# schachzwerg.net
KiCad netlist of a schematic drawn in EAGLE
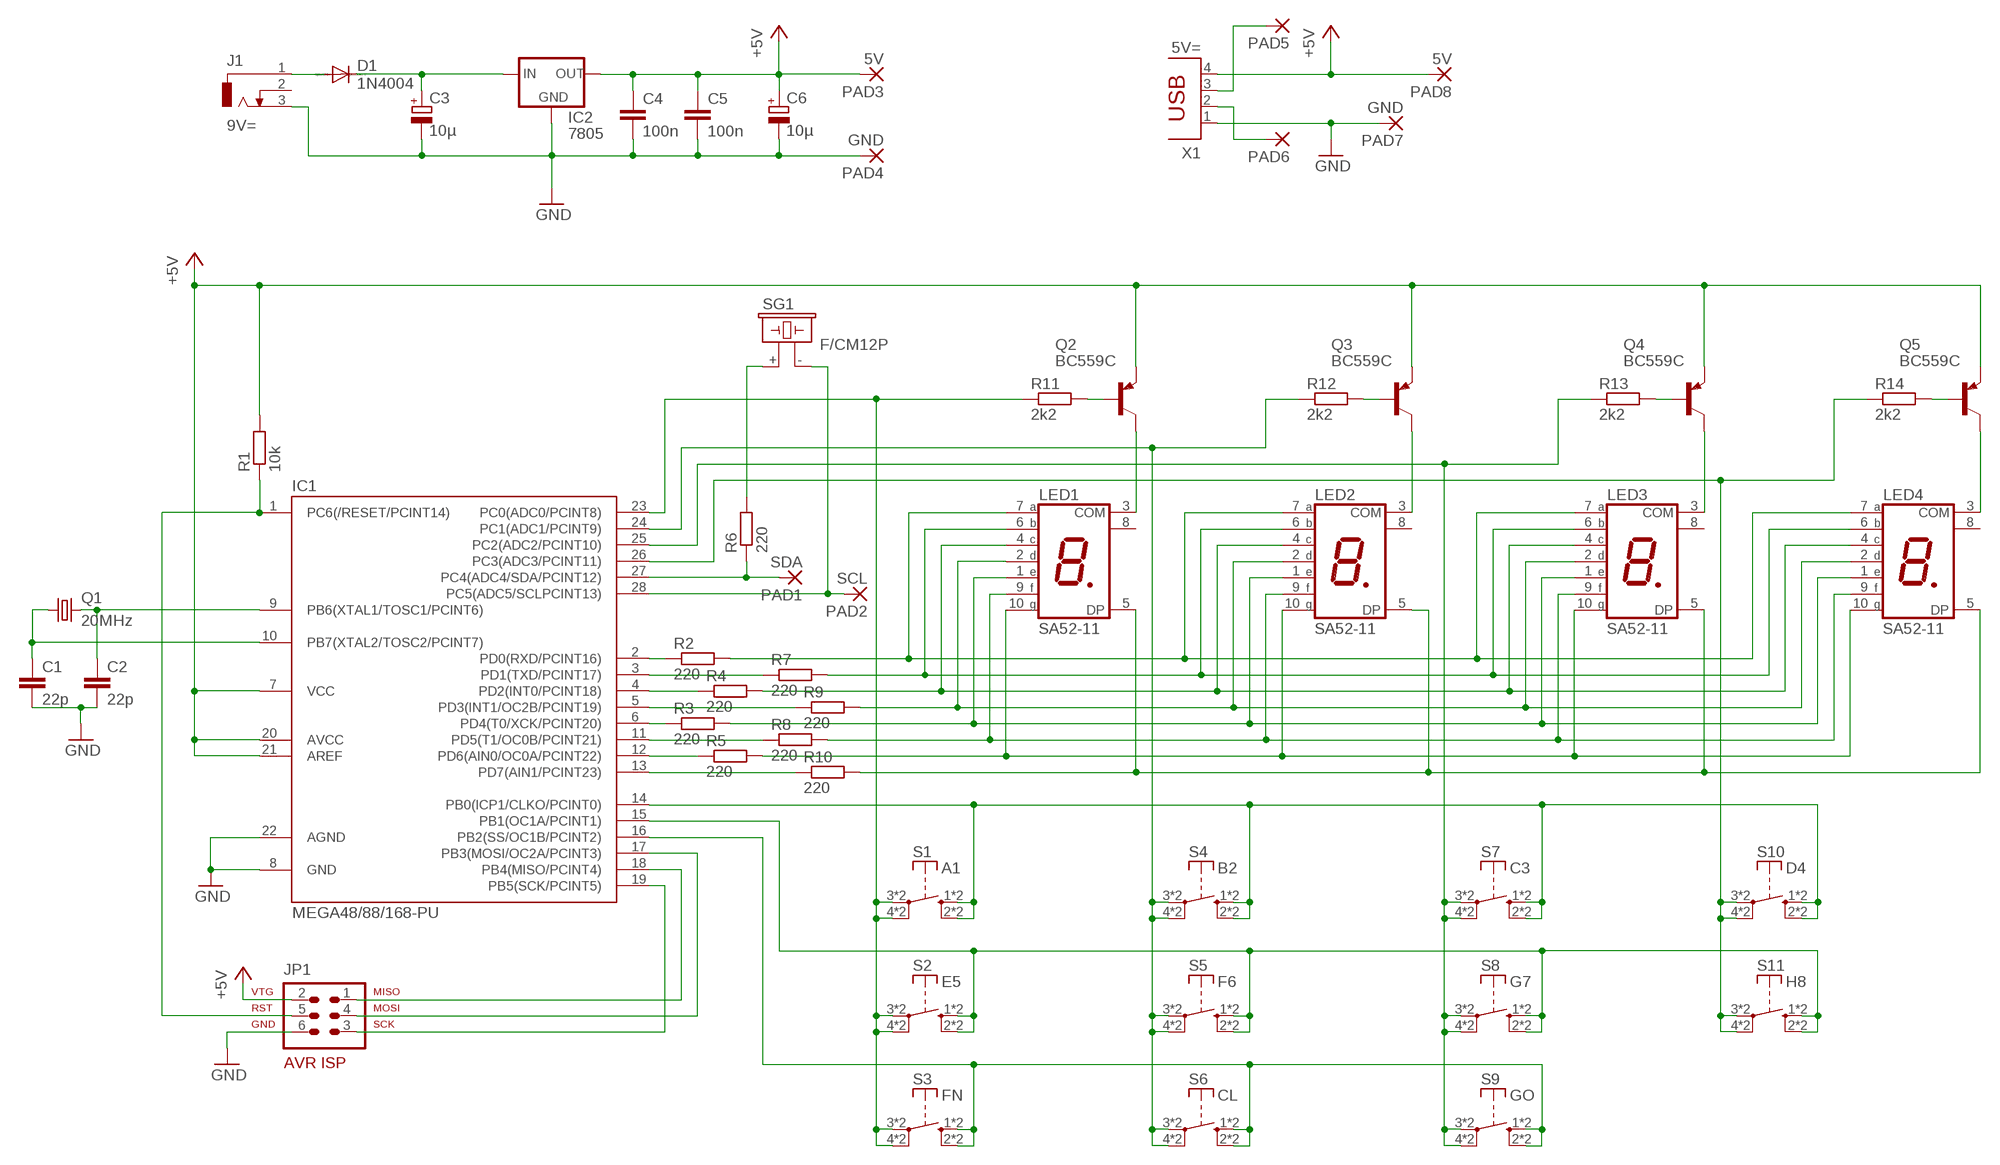
[diagram p0: schematic, sheet 1]

(export (version "E")
  (design (tool "Eeschema 10.0.6"))
  (components
    (comp (ref "C1")
      (value "22p")
      (footprint "eagle-import:C025-025X050")
      (libsource (lib "eagle-import") (part "C-EU025-025X050"))
    )
    (comp (ref "C2")
      (value "22p")
      (footprint "eagle-import:C025-025X050")
      (libsource (lib "eagle-import") (part "C-EU025-025X050"))
    )
    (comp (ref "C3")
      (value "10µ")
      (footprint "eagle-import:E2,5-5")
      (libsource (lib "eagle-import") (part "CPOL-EUE2.5-5"))
    )
    (comp (ref "C4")
      (value "100n")
      (footprint "eagle-import:C025-025X050")
      (libsource (lib "eagle-import") (part "C-EU025-025X050"))
    )
    (comp (ref "C5")
      (value "100n")
      (footprint "eagle-import:C025-025X050")
      (libsource (lib "eagle-import") (part "C-EU025-025X050"))
    )
    (comp (ref "C6")
      (value "10µ")
      (footprint "eagle-import:E2,5-5")
      (libsource (lib "eagle-import") (part "CPOL-EUE2.5-5"))
    )
    (comp (ref "D1")
      (value "1N4004")
      (footprint "eagle-import:DO41-10")
      (libsource (lib "eagle-import") (part "1N4004"))
    )
    (comp (ref "IC1")
      (value "MEGA48/88/168-PU")
      (footprint "eagle-import:DIL28-3")
      (libsource (lib "eagle-import") (part "MEGA48/88/168-PU"))
    )
    (comp (ref "IC2")
      (value "7805")
      (footprint "eagle-import:78XXS")
      (libsource (lib "eagle-import") (part "78XXS"))
    )
    (comp (ref "J1")
      (value "9V=")
      (footprint "eagle-import:DCJ0303")
      (libsource (lib "eagle-import") (part "DCJ0303"))
    )
    (comp (ref "JP1")
      (value "AVR-ISP-6")
      (footprint "eagle-import:AVR-ISP-6")
      (libsource (lib "eagle-import") (part "AVR-ISP-6"))
    )
    (comp (ref "LED1")
      (value "SA52-11")
      (footprint "eagle-import:SA52-11")
      (libsource (lib "eagle-import") (part "7-SEG_SA52-11"))
    )
    (comp (ref "LED2")
      (value "SA52-11")
      (footprint "eagle-import:SA52-11")
      (libsource (lib "eagle-import") (part "7-SEG_SA52-11"))
    )
    (comp (ref "LED3")
      (value "SA52-11")
      (footprint "eagle-import:SA52-11")
      (libsource (lib "eagle-import") (part "7-SEG_SA52-11"))
    )
    (comp (ref "LED4")
      (value "SA52-11")
      (footprint "eagle-import:SA52-11")
      (libsource (lib "eagle-import") (part "7-SEG_SA52-11"))
    )
    (comp (ref "PAD1")
      (value "SDA")
      (footprint "eagle-import:1,6_0,8")
      (libsource (lib "eagle-import") (part "1,6/0,8"))
    )
    (comp (ref "PAD2")
      (value "SCL")
      (footprint "eagle-import:1,6_0,8")
      (libsource (lib "eagle-import") (part "1,6/0,8"))
    )
    (comp (ref "PAD3")
      (value "5V")
      (footprint "eagle-import:1,6_0,8")
      (libsource (lib "eagle-import") (part "1,6/0,8"))
    )
    (comp (ref "PAD4")
      (value "GND")
      (footprint "eagle-import:1,6_0,8")
      (libsource (lib "eagle-import") (part "1,6/0,8"))
    )
    (comp (ref "PAD5")
      (value "1,6/0,8")
      (footprint "eagle-import:1,6_0,8")
      (libsource (lib "eagle-import") (part "1,6/0,8"))
    )
    (comp (ref "PAD6")
      (value "1,6/0,8")
      (footprint "eagle-import:1,6_0,8")
      (libsource (lib "eagle-import") (part "1,6/0,8"))
    )
    (comp (ref "PAD7")
      (value "GND")
      (footprint "eagle-import:1,6_0,8")
      (libsource (lib "eagle-import") (part "1,6/0,8"))
    )
    (comp (ref "PAD8")
      (value "5V")
      (footprint "eagle-import:1,6_0,8")
      (libsource (lib "eagle-import") (part "1,6/0,8"))
    )
    (comp (ref "Q1")
      (value "20MHz")
      (footprint "eagle-import:HC49_S")
      (libsource (lib "eagle-import") (part "CRYSTALHC49S"))
    )
    (comp (ref "Q2")
      (value "BC559C")
      (footprint "eagle-import:TO92-EBC")
      (libsource (lib "eagle-import") (part "BC559C"))
    )
    (comp (ref "Q3")
      (value "BC559C")
      (footprint "eagle-import:TO92-EBC")
      (libsource (lib "eagle-import") (part "BC559C"))
    )
    (comp (ref "Q4")
      (value "BC559C")
      (footprint "eagle-import:TO92-EBC")
      (libsource (lib "eagle-import") (part "BC559C"))
    )
    (comp (ref "Q5")
      (value "BC559C")
      (footprint "eagle-import:TO92-EBC")
      (libsource (lib "eagle-import") (part "BC559C"))
    )
    (comp (ref "R1")
      (value "10k")
      (footprint "eagle-import:0204_7")
      (libsource (lib "eagle-import") (part "R-EU_0204/7"))
    )
    (comp (ref "R2")
      (value "220")
      (footprint "eagle-import:0204_7")
      (libsource (lib "eagle-import") (part "R-EU_0204/7"))
    )
    (comp (ref "R3")
      (value "220")
      (footprint "eagle-import:0204_7")
      (libsource (lib "eagle-import") (part "R-EU_0204/7"))
    )
    (comp (ref "R4")
      (value "220")
      (footprint "eagle-import:0204_7")
      (libsource (lib "eagle-import") (part "R-EU_0204/7"))
    )
    (comp (ref "R5")
      (value "220")
      (footprint "eagle-import:0204_7")
      (libsource (lib "eagle-import") (part "R-EU_0204/7"))
    )
    (comp (ref "R6")
      (value "220")
      (footprint "eagle-import:0204_7")
      (libsource (lib "eagle-import") (part "R-EU_0204/7"))
    )
    (comp (ref "R7")
      (value "220")
      (footprint "eagle-import:0204_7")
      (libsource (lib "eagle-import") (part "R-EU_0204/7"))
    )
    (comp (ref "R8")
      (value "220")
      (footprint "eagle-import:0204_7")
      (libsource (lib "eagle-import") (part "R-EU_0204/7"))
    )
    (comp (ref "R9")
      (value "220")
      (footprint "eagle-import:0204_7")
      (libsource (lib "eagle-import") (part "R-EU_0204/7"))
    )
    (comp (ref "R10")
      (value "220")
      (footprint "eagle-import:0204_7")
      (libsource (lib "eagle-import") (part "R-EU_0204/7"))
    )
    (comp (ref "R11")
      (value "2k2")
      (footprint "eagle-import:0204_7")
      (libsource (lib "eagle-import") (part "R-EU_0204/7"))
    )
    (comp (ref "R12")
      (value "2k2")
      (footprint "eagle-import:0204_7")
      (libsource (lib "eagle-import") (part "R-EU_0204/7"))
    )
    (comp (ref "R13")
      (value "2k2")
      (footprint "eagle-import:0204_7")
      (libsource (lib "eagle-import") (part "R-EU_0204/7"))
    )
    (comp (ref "R14")
      (value "2k2")
      (footprint "eagle-import:0204_7")
      (libsource (lib "eagle-import") (part "R-EU_0204/7"))
    )
    (comp (ref "S1")
      (value "A1")
      (footprint "eagle-import:DT6")
      (libsource (lib "eagle-import") (part "DT6"))
    )
    (comp (ref "S2")
      (value "E5")
      (footprint "eagle-import:DT6")
      (libsource (lib "eagle-import") (part "DT6"))
    )
    (comp (ref "S3")
      (value "FN")
      (footprint "eagle-import:DT6")
      (libsource (lib "eagle-import") (part "DT6"))
    )
    (comp (ref "S4")
      (value "B2")
      (footprint "eagle-import:DT6")
      (libsource (lib "eagle-import") (part "DT6"))
    )
    (comp (ref "S5")
      (value "F6")
      (footprint "eagle-import:DT6")
      (libsource (lib "eagle-import") (part "DT6"))
    )
    (comp (ref "S6")
      (value "CL")
      (footprint "eagle-import:DT6")
      (libsource (lib "eagle-import") (part "DT6"))
    )
    (comp (ref "S7")
      (value "C3")
      (footprint "eagle-import:DT6")
      (libsource (lib "eagle-import") (part "DT6"))
    )
    (comp (ref "S8")
      (value "G7")
      (footprint "eagle-import:DT6")
      (libsource (lib "eagle-import") (part "DT6"))
    )
    (comp (ref "S9")
      (value "GO")
      (footprint "eagle-import:DT6")
      (libsource (lib "eagle-import") (part "DT6"))
    )
    (comp (ref "S10")
      (value "D4")
      (footprint "eagle-import:DT6")
      (libsource (lib "eagle-import") (part "DT6"))
    )
    (comp (ref "S11")
      (value "H8")
      (footprint "eagle-import:DT6")
      (libsource (lib "eagle-import") (part "DT6"))
    )
    (comp (ref "SG1")
      (value "F/CM12P")
      (footprint "eagle-import:F_CM12P")
      (libsource (lib "eagle-import") (part "F/CM12P"))
    )
    (comp (ref "X1")
      (value "5V=")
      (footprint "eagle-import:PN87520")
      (libsource (lib "eagle-import") (part "PN87520"))
    )
  )
  (nets
    (net (code "1") (name "+5V") (class "Default")
      (node (ref "C4") (pin "1") (pinfunction "1_1") (pintype "passive"))
      (node (ref "C5") (pin "1") (pinfunction "1_1") (pintype "passive"))
      (node (ref "C6") (pin "+") (pinfunction "+_+") (pintype "passive"))
      (node (ref "IC1") (pin "20") (pinfunction "AVCC_20") (pintype "passive"))
      (node (ref "IC1") (pin "21") (pinfunction "AREF_21") (pintype "passive"))
      (node (ref "IC1") (pin "7") (pinfunction "VCC_7") (pintype "power_in"))
      (node (ref "IC2") (pin "OUT") (pinfunction "OUT_OUT") (pintype "passive"))
      (node (ref "JP1") (pin "2") (pinfunction "2_2") (pintype "passive"))
      (node (ref "PAD3") (pin "1") (pinfunction "P_1") (pintype "passive"))
      (node (ref "PAD8") (pin "1") (pinfunction "P_1") (pintype "passive"))
      (node (ref "Q2") (pin "E") (pinfunction "E_E") (pintype "passive"))
      (node (ref "Q3") (pin "E") (pinfunction "E_E") (pintype "passive"))
      (node (ref "Q4") (pin "E") (pinfunction "E_E") (pintype "passive"))
      (node (ref "Q5") (pin "E") (pinfunction "E_E") (pintype "passive"))
      (node (ref "R1") (pin "2") (pinfunction "2_2") (pintype "passive"))
      (node (ref "X1") (pin "4") (pinfunction "4_4") (pintype "passive"))
    )
    (net (code "2") (name "GND") (class "Default")
      (node (ref "C1") (pin "2") (pinfunction "2_2") (pintype "passive"))
      (node (ref "C2") (pin "2") (pinfunction "2_2") (pintype "passive"))
      (node (ref "C3") (pin "-") (pinfunction "-_-") (pintype "passive"))
      (node (ref "C4") (pin "2") (pinfunction "2_2") (pintype "passive"))
      (node (ref "C5") (pin "2") (pinfunction "2_2") (pintype "passive"))
      (node (ref "C6") (pin "-") (pinfunction "-_-") (pintype "passive"))
      (node (ref "IC1") (pin "22") (pinfunction "AGND_22") (pintype "power_in"))
      (node (ref "IC1") (pin "8") (pinfunction "GND_8") (pintype "power_in"))
      (node (ref "IC2") (pin "GND") (pinfunction "GND_GND") (pintype "input"))
      (node (ref "J1") (pin "3") (pinfunction "3_3") (pintype "passive"))
      (node (ref "JP1") (pin "6") (pinfunction "6_6") (pintype "passive"))
      (node (ref "PAD4") (pin "1") (pinfunction "P_1") (pintype "passive"))
      (node (ref "PAD7") (pin "1") (pinfunction "P_1") (pintype "passive"))
      (node (ref "X1") (pin "1") (pinfunction "1_1") (pintype "passive"))
    )
    (net (code "3") (name "Net-(C3-Pad+)") (class "Default")
      (node (ref "C3") (pin "+") (pinfunction "+_+") (pintype "passive"))
      (node (ref "D1") (pin "C") (pinfunction "C_C") (pintype "passive"))
      (node (ref "IC2") (pin "IN") (pinfunction "IN_IN") (pintype "input"))
    )
    (net (code "4") (name "Net-(D1-PadA)") (class "Default")
      (node (ref "D1") (pin "A") (pinfunction "A_A") (pintype "passive"))
      (node (ref "J1") (pin "1") (pinfunction "1_1") (pintype "passive"))
    )
    (net (code "5") (name "Net-(IC1-PB0(ICP1{slash}CLKO{slash}PCINT0))") (class "Default")
      (node (ref "IC1") (pin "14") (pinfunction "PB0(ICP1/CLKO/PCINT0)_14") (pintype "bidirectional"))
      (node (ref "S1") (pin "1") (pinfunction "S_1") (pintype "passive"))
      (node (ref "S1") (pin "2") (pinfunction "S_2") (pintype "passive"))
      (node (ref "S1") (pin "5") (pinfunction "S_5") (pintype "passive"))
      (node (ref "S1") (pin "6") (pinfunction "S_6") (pintype "passive"))
      (node (ref "S10") (pin "1") (pinfunction "S_1") (pintype "passive"))
      (node (ref "S10") (pin "2") (pinfunction "S_2") (pintype "passive"))
      (node (ref "S10") (pin "5") (pinfunction "S_5") (pintype "passive"))
      (node (ref "S10") (pin "6") (pinfunction "S_6") (pintype "passive"))
      (node (ref "S4") (pin "1") (pinfunction "S_1") (pintype "passive"))
      (node (ref "S4") (pin "2") (pinfunction "S_2") (pintype "passive"))
      (node (ref "S4") (pin "5") (pinfunction "S_5") (pintype "passive"))
      (node (ref "S4") (pin "6") (pinfunction "S_6") (pintype "passive"))
      (node (ref "S7") (pin "1") (pinfunction "S_1") (pintype "passive"))
      (node (ref "S7") (pin "2") (pinfunction "S_2") (pintype "passive"))
      (node (ref "S7") (pin "5") (pinfunction "S_5") (pintype "passive"))
      (node (ref "S7") (pin "6") (pinfunction "S_6") (pintype "passive"))
    )
    (net (code "6") (name "Net-(IC1-PB1(OC1A{slash}PCINT1))") (class "Default")
      (node (ref "IC1") (pin "15") (pinfunction "PB1(OC1A/PCINT1)_15") (pintype "bidirectional"))
      (node (ref "S11") (pin "1") (pinfunction "S_1") (pintype "passive"))
      (node (ref "S11") (pin "2") (pinfunction "S_2") (pintype "passive"))
      (node (ref "S11") (pin "5") (pinfunction "S_5") (pintype "passive"))
      (node (ref "S11") (pin "6") (pinfunction "S_6") (pintype "passive"))
      (node (ref "S2") (pin "1") (pinfunction "S_1") (pintype "passive"))
      (node (ref "S2") (pin "2") (pinfunction "S_2") (pintype "passive"))
      (node (ref "S2") (pin "5") (pinfunction "S_5") (pintype "passive"))
      (node (ref "S2") (pin "6") (pinfunction "S_6") (pintype "passive"))
      (node (ref "S5") (pin "1") (pinfunction "S_1") (pintype "passive"))
      (node (ref "S5") (pin "2") (pinfunction "S_2") (pintype "passive"))
      (node (ref "S5") (pin "5") (pinfunction "S_5") (pintype "passive"))
      (node (ref "S5") (pin "6") (pinfunction "S_6") (pintype "passive"))
      (node (ref "S8") (pin "1") (pinfunction "S_1") (pintype "passive"))
      (node (ref "S8") (pin "2") (pinfunction "S_2") (pintype "passive"))
      (node (ref "S8") (pin "5") (pinfunction "S_5") (pintype "passive"))
      (node (ref "S8") (pin "6") (pinfunction "S_6") (pintype "passive"))
    )
    (net (code "7") (name "Net-(IC1-PB2(SS{slash}OC1B{slash}PCINT2))") (class "Default")
      (node (ref "IC1") (pin "16") (pinfunction "PB2(SS/OC1B/PCINT2)_16") (pintype "bidirectional"))
      (node (ref "S3") (pin "1") (pinfunction "S_1") (pintype "passive"))
      (node (ref "S3") (pin "2") (pinfunction "S_2") (pintype "passive"))
      (node (ref "S3") (pin "5") (pinfunction "S_5") (pintype "passive"))
      (node (ref "S3") (pin "6") (pinfunction "S_6") (pintype "passive"))
      (node (ref "S6") (pin "1") (pinfunction "S_1") (pintype "passive"))
      (node (ref "S6") (pin "2") (pinfunction "S_2") (pintype "passive"))
      (node (ref "S6") (pin "5") (pinfunction "S_5") (pintype "passive"))
      (node (ref "S6") (pin "6") (pinfunction "S_6") (pintype "passive"))
      (node (ref "S9") (pin "1") (pinfunction "S_1") (pintype "passive"))
      (node (ref "S9") (pin "2") (pinfunction "S_2") (pintype "passive"))
      (node (ref "S9") (pin "5") (pinfunction "S_5") (pintype "passive"))
      (node (ref "S9") (pin "6") (pinfunction "S_6") (pintype "passive"))
    )
    (net (code "8") (name "Net-(IC1-PB3(MOSI{slash}OC2A{slash}PCINT3))") (class "Default")
      (node (ref "IC1") (pin "17") (pinfunction "PB3(MOSI/OC2A/PCINT3)_17") (pintype "bidirectional"))
      (node (ref "JP1") (pin "4") (pinfunction "4_4") (pintype "passive"))
    )
    (net (code "9") (name "Net-(IC1-PB4(MISO{slash}PCINT4))") (class "Default")
      (node (ref "IC1") (pin "18") (pinfunction "PB4(MISO/PCINT4)_18") (pintype "bidirectional"))
      (node (ref "JP1") (pin "1") (pinfunction "1_1") (pintype "passive"))
    )
    (net (code "10") (name "Net-(IC1-PB5(SCK{slash}PCINT5))") (class "Default")
      (node (ref "IC1") (pin "19") (pinfunction "PB5(SCK/PCINT5)_19") (pintype "bidirectional"))
      (node (ref "JP1") (pin "3") (pinfunction "3_3") (pintype "passive"))
    )
    (net (code "11") (name "Net-(IC1-PB6(XTAL1{slash}TOSC1{slash}PCINT6))") (class "Default")
      (node (ref "C2") (pin "1") (pinfunction "1_1") (pintype "passive"))
      (node (ref "IC1") (pin "9") (pinfunction "PB6(XTAL1/TOSC1/PCINT6)_9") (pintype "bidirectional"))
      (node (ref "Q1") (pin "2") (pinfunction "2_2") (pintype "passive"))
    )
    (net (code "12") (name "Net-(IC1-PB7(XTAL2{slash}TOSC2{slash}PCINT7))") (class "Default")
      (node (ref "C1") (pin "1") (pinfunction "1_1") (pintype "passive"))
      (node (ref "IC1") (pin "10") (pinfunction "PB7(XTAL2/TOSC2/PCINT7)_10") (pintype "bidirectional"))
      (node (ref "Q1") (pin "1") (pinfunction "1_1") (pintype "passive"))
    )
    (net (code "13") (name "Net-(IC1-PC0(ADC0{slash}PCINT8))") (class "Default")
      (node (ref "IC1") (pin "23") (pinfunction "PC0(ADC0/PCINT8)_23") (pintype "bidirectional"))
      (node (ref "R11") (pin "1") (pinfunction "1_1") (pintype "passive"))
      (node (ref "S1") (pin "3") (pinfunction "P_3") (pintype "passive"))
      (node (ref "S1") (pin "4") (pinfunction "P_4") (pintype "passive"))
      (node (ref "S1") (pin "7") (pinfunction "P_7") (pintype "passive"))
      (node (ref "S1") (pin "8") (pinfunction "P_8") (pintype "passive"))
      (node (ref "S2") (pin "3") (pinfunction "P_3") (pintype "passive"))
      (node (ref "S2") (pin "4") (pinfunction "P_4") (pintype "passive"))
      (node (ref "S2") (pin "7") (pinfunction "P_7") (pintype "passive"))
      (node (ref "S2") (pin "8") (pinfunction "P_8") (pintype "passive"))
      (node (ref "S3") (pin "3") (pinfunction "P_3") (pintype "passive"))
      (node (ref "S3") (pin "4") (pinfunction "P_4") (pintype "passive"))
      (node (ref "S3") (pin "7") (pinfunction "P_7") (pintype "passive"))
      (node (ref "S3") (pin "8") (pinfunction "P_8") (pintype "passive"))
    )
    (net (code "14") (name "Net-(IC1-PC1(ADC1{slash}PCINT9))") (class "Default")
      (node (ref "IC1") (pin "24") (pinfunction "PC1(ADC1/PCINT9)_24") (pintype "bidirectional"))
      (node (ref "R12") (pin "1") (pinfunction "1_1") (pintype "passive"))
      (node (ref "S4") (pin "3") (pinfunction "P_3") (pintype "passive"))
      (node (ref "S4") (pin "4") (pinfunction "P_4") (pintype "passive"))
      (node (ref "S4") (pin "7") (pinfunction "P_7") (pintype "passive"))
      (node (ref "S4") (pin "8") (pinfunction "P_8") (pintype "passive"))
      (node (ref "S5") (pin "3") (pinfunction "P_3") (pintype "passive"))
      (node (ref "S5") (pin "4") (pinfunction "P_4") (pintype "passive"))
      (node (ref "S5") (pin "7") (pinfunction "P_7") (pintype "passive"))
      (node (ref "S5") (pin "8") (pinfunction "P_8") (pintype "passive"))
      (node (ref "S6") (pin "3") (pinfunction "P_3") (pintype "passive"))
      (node (ref "S6") (pin "4") (pinfunction "P_4") (pintype "passive"))
      (node (ref "S6") (pin "7") (pinfunction "P_7") (pintype "passive"))
      (node (ref "S6") (pin "8") (pinfunction "P_8") (pintype "passive"))
    )
    (net (code "15") (name "Net-(IC1-PC2(ADC2{slash}PCINT10))") (class "Default")
      (node (ref "IC1") (pin "25") (pinfunction "PC2(ADC2/PCINT10)_25") (pintype "bidirectional"))
      (node (ref "R13") (pin "1") (pinfunction "1_1") (pintype "passive"))
      (node (ref "S7") (pin "3") (pinfunction "P_3") (pintype "passive"))
      (node (ref "S7") (pin "4") (pinfunction "P_4") (pintype "passive"))
      (node (ref "S7") (pin "7") (pinfunction "P_7") (pintype "passive"))
      (node (ref "S7") (pin "8") (pinfunction "P_8") (pintype "passive"))
      (node (ref "S8") (pin "3") (pinfunction "P_3") (pintype "passive"))
      (node (ref "S8") (pin "4") (pinfunction "P_4") (pintype "passive"))
      (node (ref "S8") (pin "7") (pinfunction "P_7") (pintype "passive"))
      (node (ref "S8") (pin "8") (pinfunction "P_8") (pintype "passive"))
      (node (ref "S9") (pin "3") (pinfunction "P_3") (pintype "passive"))
      (node (ref "S9") (pin "4") (pinfunction "P_4") (pintype "passive"))
      (node (ref "S9") (pin "7") (pinfunction "P_7") (pintype "passive"))
      (node (ref "S9") (pin "8") (pinfunction "P_8") (pintype "passive"))
    )
    (net (code "16") (name "Net-(IC1-PC3(ADC3{slash}PCINT11))") (class "Default")
      (node (ref "IC1") (pin "26") (pinfunction "PC3(ADC3/PCINT11)_26") (pintype "bidirectional"))
      (node (ref "R14") (pin "1") (pinfunction "1_1") (pintype "passive"))
      (node (ref "S10") (pin "3") (pinfunction "P_3") (pintype "passive"))
      (node (ref "S10") (pin "4") (pinfunction "P_4") (pintype "passive"))
      (node (ref "S10") (pin "7") (pinfunction "P_7") (pintype "passive"))
      (node (ref "S10") (pin "8") (pinfunction "P_8") (pintype "passive"))
      (node (ref "S11") (pin "3") (pinfunction "P_3") (pintype "passive"))
      (node (ref "S11") (pin "4") (pinfunction "P_4") (pintype "passive"))
      (node (ref "S11") (pin "7") (pinfunction "P_7") (pintype "passive"))
      (node (ref "S11") (pin "8") (pinfunction "P_8") (pintype "passive"))
    )
    (net (code "17") (name "Net-(IC1-PC4(ADC4{slash}SDA{slash}PCINT12))") (class "Default")
      (node (ref "IC1") (pin "27") (pinfunction "PC4(ADC4/SDA/PCINT12)_27") (pintype "bidirectional"))
      (node (ref "PAD1") (pin "1") (pinfunction "P_1") (pintype "passive"))
      (node (ref "R6") (pin "1") (pinfunction "1_1") (pintype "passive"))
    )
    (net (code "18") (name "Net-(IC1-PC5(ADC5{slash}SCLPCINT13))") (class "Default")
      (node (ref "IC1") (pin "28") (pinfunction "PC5(ADC5/SCLPCINT13)_28") (pintype "bidirectional"))
      (node (ref "PAD2") (pin "1") (pinfunction "P_1") (pintype "passive"))
      (node (ref "SG1") (pin "-") (pinfunction "2_-") (pintype "passive"))
    )
    (net (code "19") (name "Net-(IC1-PC6({slash}RESET{slash}PCINT14))") (class "Default")
      (node (ref "IC1") (pin "1") (pinfunction "PC6(/RESET/PCINT14)_1") (pintype "bidirectional"))
      (node (ref "JP1") (pin "5") (pinfunction "5_5") (pintype "passive"))
      (node (ref "R1") (pin "1") (pinfunction "1_1") (pintype "passive"))
    )
    (net (code "20") (name "Net-(IC1-PD0(RXD{slash}PCINT16))") (class "Default")
      (node (ref "IC1") (pin "2") (pinfunction "PD0(RXD/PCINT16)_2") (pintype "bidirectional"))
      (node (ref "R2") (pin "1") (pinfunction "1_1") (pintype "passive"))
    )
    (net (code "21") (name "Net-(IC1-PD1(TXD{slash}PCINT17))") (class "Default")
      (node (ref "IC1") (pin "3") (pinfunction "PD1(TXD/PCINT17)_3") (pintype "bidirectional"))
      (node (ref "R7") (pin "1") (pinfunction "1_1") (pintype "passive"))
    )
    (net (code "22") (name "Net-(IC1-PD2(INT0{slash}PCINT18))") (class "Default")
      (node (ref "IC1") (pin "4") (pinfunction "PD2(INT0/PCINT18)_4") (pintype "bidirectional"))
      (node (ref "R4") (pin "1") (pinfunction "1_1") (pintype "passive"))
    )
    (net (code "23") (name "Net-(IC1-PD3(INT1{slash}OC2B{slash}PCINT19))") (class "Default")
      (node (ref "IC1") (pin "5") (pinfunction "PD3(INT1/OC2B/PCINT19)_5") (pintype "bidirectional"))
      (node (ref "R9") (pin "1") (pinfunction "1_1") (pintype "passive"))
    )
    (net (code "24") (name "Net-(IC1-PD4(T0{slash}XCK{slash}PCINT20))") (class "Default")
      (node (ref "IC1") (pin "6") (pinfunction "PD4(T0/XCK/PCINT20)_6") (pintype "bidirectional"))
      (node (ref "R3") (pin "1") (pinfunction "1_1") (pintype "passive"))
    )
    (net (code "25") (name "Net-(IC1-PD5(T1{slash}OC0B{slash}PCINT21))") (class "Default")
      (node (ref "IC1") (pin "11") (pinfunction "PD5(T1/OC0B/PCINT21)_11") (pintype "bidirectional"))
      (node (ref "R8") (pin "1") (pinfunction "1_1") (pintype "passive"))
    )
    (net (code "26") (name "Net-(IC1-PD6(AIN0{slash}OC0A{slash}PCINT22))") (class "Default")
      (node (ref "IC1") (pin "12") (pinfunction "PD6(AIN0/OC0A/PCINT22)_12") (pintype "bidirectional"))
      (node (ref "R5") (pin "1") (pinfunction "1_1") (pintype "passive"))
    )
    (net (code "27") (name "Net-(IC1-PD7(AIN1{slash}PCINT23))") (class "Default")
      (node (ref "IC1") (pin "13") (pinfunction "PD7(AIN1/PCINT23)_13") (pintype "bidirectional"))
      (node (ref "R10") (pin "1") (pinfunction "1_1") (pintype "passive"))
    )
    (net (code "28") (name "Net-(LED1-A)") (class "Default")
      (node (ref "LED1") (pin "7") (pinfunction "A_7") (pintype "passive"))
      (node (ref "LED2") (pin "7") (pinfunction "A_7") (pintype "passive"))
      (node (ref "LED3") (pin "7") (pinfunction "A_7") (pintype "passive"))
      (node (ref "LED4") (pin "7") (pinfunction "A_7") (pintype "passive"))
      (node (ref "R2") (pin "2") (pinfunction "2_2") (pintype "passive"))
    )
    (net (code "29") (name "Net-(LED1-B)") (class "Default")
      (node (ref "LED1") (pin "6") (pinfunction "B_6") (pintype "passive"))
      (node (ref "LED2") (pin "6") (pinfunction "B_6") (pintype "passive"))
      (node (ref "LED3") (pin "6") (pinfunction "B_6") (pintype "passive"))
      (node (ref "LED4") (pin "6") (pinfunction "B_6") (pintype "passive"))
      (node (ref "R7") (pin "2") (pinfunction "2_2") (pintype "passive"))
    )
    (net (code "30") (name "Net-(LED1-C)") (class "Default")
      (node (ref "LED1") (pin "4") (pinfunction "C_4") (pintype "passive"))
      (node (ref "LED2") (pin "4") (pinfunction "C_4") (pintype "passive"))
      (node (ref "LED3") (pin "4") (pinfunction "C_4") (pintype "passive"))
      (node (ref "LED4") (pin "4") (pinfunction "C_4") (pintype "passive"))
      (node (ref "R4") (pin "2") (pinfunction "2_2") (pintype "passive"))
    )
    (net (code "31") (name "Net-(LED1-COM-Pad3)") (class "Default")
      (node (ref "LED1") (pin "3") (pinfunction "COM_3") (pintype "passive"))
      (node (ref "Q2") (pin "C") (pinfunction "C_C") (pintype "passive"))
    )
    (net (code "32") (name "Net-(LED1-D)") (class "Default")
      (node (ref "LED1") (pin "2") (pinfunction "D_2") (pintype "passive"))
      (node (ref "LED2") (pin "2") (pinfunction "D_2") (pintype "passive"))
      (node (ref "LED3") (pin "2") (pinfunction "D_2") (pintype "passive"))
      (node (ref "LED4") (pin "2") (pinfunction "D_2") (pintype "passive"))
      (node (ref "R9") (pin "2") (pinfunction "2_2") (pintype "passive"))
    )
    (net (code "33") (name "Net-(LED1-DP)") (class "Default")
      (node (ref "LED1") (pin "5") (pinfunction "DP_5") (pintype "passive"))
      (node (ref "LED2") (pin "5") (pinfunction "DP_5") (pintype "passive"))
      (node (ref "LED3") (pin "5") (pinfunction "DP_5") (pintype "passive"))
      (node (ref "LED4") (pin "5") (pinfunction "DP_5") (pintype "passive"))
      (node (ref "R10") (pin "2") (pinfunction "2_2") (pintype "passive"))
    )
    (net (code "34") (name "Net-(LED1-E)") (class "Default")
      (node (ref "LED1") (pin "1") (pinfunction "E_1") (pintype "passive"))
      (node (ref "LED2") (pin "1") (pinfunction "E_1") (pintype "passive"))
      (node (ref "LED3") (pin "1") (pinfunction "E_1") (pintype "passive"))
      (node (ref "LED4") (pin "1") (pinfunction "E_1") (pintype "passive"))
      (node (ref "R3") (pin "2") (pinfunction "2_2") (pintype "passive"))
    )
    (net (code "35") (name "Net-(LED1-F)") (class "Default")
      (node (ref "LED1") (pin "9") (pinfunction "F_9") (pintype "passive"))
      (node (ref "LED2") (pin "9") (pinfunction "F_9") (pintype "passive"))
      (node (ref "LED3") (pin "9") (pinfunction "F_9") (pintype "passive"))
      (node (ref "LED4") (pin "9") (pinfunction "F_9") (pintype "passive"))
      (node (ref "R8") (pin "2") (pinfunction "2_2") (pintype "passive"))
    )
    (net (code "36") (name "Net-(LED1-G)") (class "Default")
      (node (ref "LED1") (pin "10") (pinfunction "G_10") (pintype "passive"))
      (node (ref "LED2") (pin "10") (pinfunction "G_10") (pintype "passive"))
      (node (ref "LED3") (pin "10") (pinfunction "G_10") (pintype "passive"))
      (node (ref "LED4") (pin "10") (pinfunction "G_10") (pintype "passive"))
      (node (ref "R5") (pin "2") (pinfunction "2_2") (pintype "passive"))
    )
    (net (code "37") (name "Net-(LED2-COM-Pad3)") (class "Default")
      (node (ref "LED2") (pin "3") (pinfunction "COM_3") (pintype "passive"))
      (node (ref "Q3") (pin "C") (pinfunction "C_C") (pintype "passive"))
    )
    (net (code "38") (name "Net-(LED3-COM-Pad3)") (class "Default")
      (node (ref "LED3") (pin "3") (pinfunction "COM_3") (pintype "passive"))
      (node (ref "Q4") (pin "C") (pinfunction "C_C") (pintype "passive"))
    )
    (net (code "39") (name "Net-(LED4-COM-Pad3)") (class "Default")
      (node (ref "LED4") (pin "3") (pinfunction "COM_3") (pintype "passive"))
      (node (ref "Q5") (pin "C") (pinfunction "C_C") (pintype "passive"))
    )
    (net (code "40") (name "Net-(PAD5-P)") (class "Default")
      (node (ref "PAD5") (pin "1") (pinfunction "P_1") (pintype "passive"))
      (node (ref "X1") (pin "3") (pinfunction "3_3") (pintype "passive"))
    )
    (net (code "41") (name "Net-(PAD6-P)") (class "Default")
      (node (ref "PAD6") (pin "1") (pinfunction "P_1") (pintype "passive"))
      (node (ref "X1") (pin "2") (pinfunction "2_2") (pintype "passive"))
    )
    (net (code "42") (name "Net-(Q2-PadB)") (class "Default")
      (node (ref "Q2") (pin "B") (pinfunction "B_B") (pintype "passive"))
      (node (ref "R11") (pin "2") (pinfunction "2_2") (pintype "passive"))
    )
    (net (code "43") (name "Net-(Q3-PadB)") (class "Default")
      (node (ref "Q3") (pin "B") (pinfunction "B_B") (pintype "passive"))
      (node (ref "R12") (pin "2") (pinfunction "2_2") (pintype "passive"))
    )
    (net (code "44") (name "Net-(Q4-PadB)") (class "Default")
      (node (ref "Q4") (pin "B") (pinfunction "B_B") (pintype "passive"))
      (node (ref "R13") (pin "2") (pinfunction "2_2") (pintype "passive"))
    )
    (net (code "45") (name "Net-(Q5-PadB)") (class "Default")
      (node (ref "Q5") (pin "B") (pinfunction "B_B") (pintype "passive"))
      (node (ref "R14") (pin "2") (pinfunction "2_2") (pintype "passive"))
    )
    (net (code "46") (name "Net-(SG1-1)") (class "Default")
      (node (ref "R6") (pin "2") (pinfunction "2_2") (pintype "passive"))
      (node (ref "SG1") (pin "+") (pinfunction "1_+") (pintype "passive"))
    )
    (net (code "47") (name "unconnected-(J1-Pad2)") (class "Default")
      (node (ref "J1") (pin "2") (pinfunction "2_2") (pintype "passive"))
    )
    (net (code "48") (name "unconnected-(LED1-COM-Pad8)") (class "Default")
      (node (ref "LED1") (pin "8") (pinfunction "COM_8") (pintype "passive"))
    )
    (net (code "49") (name "unconnected-(LED2-COM-Pad8)") (class "Default")
      (node (ref "LED2") (pin "8") (pinfunction "COM_8") (pintype "passive"))
    )
    (net (code "50") (name "unconnected-(LED3-COM-Pad8)") (class "Default")
      (node (ref "LED3") (pin "8") (pinfunction "COM_8") (pintype "passive"))
    )
    (net (code "51") (name "unconnected-(LED4-COM-Pad8)") (class "Default")
      (node (ref "LED4") (pin "8") (pinfunction "COM_8") (pintype "passive"))
    )
  )
)
